# DX-HR.net
KiCad netlist of a schematic drawn in EAGLE
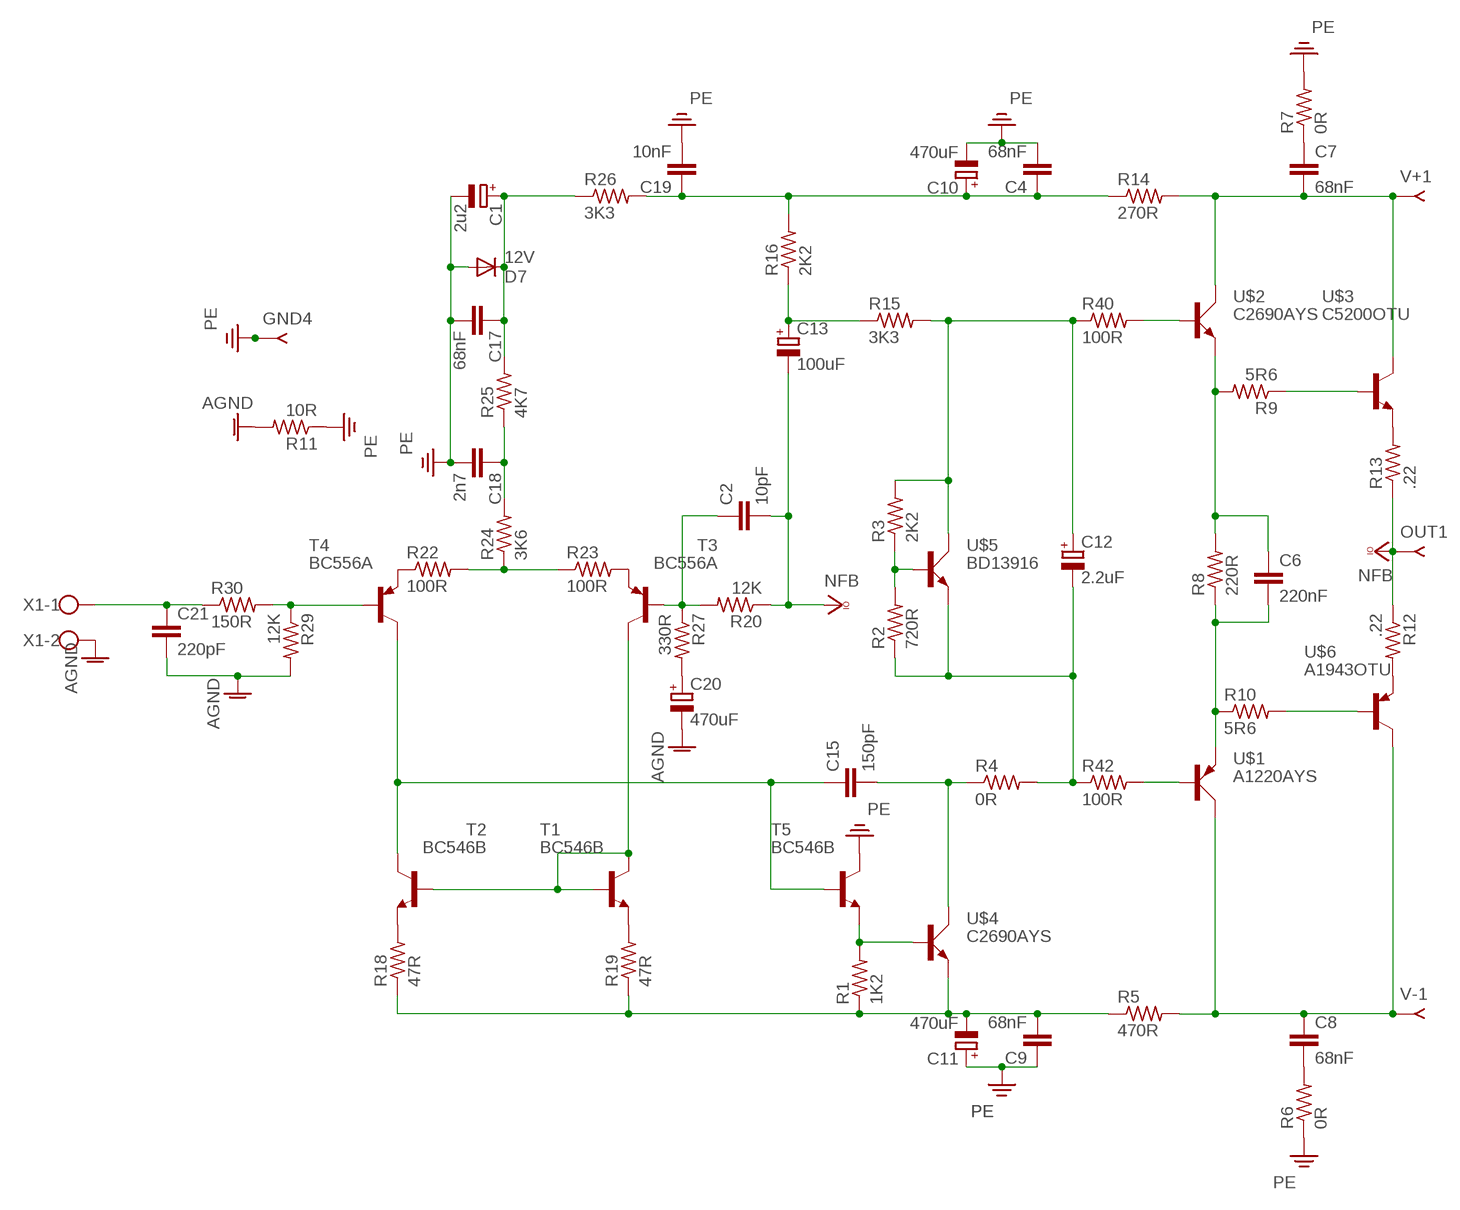
[diagram p0: schematic, sheet 1]

(export (version "E")
  (design (tool "Eeschema 10.0.6"))
  (components
    (comp (ref "C1")
      (value "2u2")
      (footprint "eagle-import:E3,5-8")
      (libsource (lib "eagle-import") (part "CPOL-EUE3.5-8"))
    )
    (comp (ref "C2")
      (value "10pF")
      (footprint "eagle-import:C102-043X133")
      (libsource (lib "eagle-import") (part "C-EU102-043X133"))
    )
    (comp (ref "C4")
      (value "68nF")
      (footprint "eagle-import:C050-055X075")
      (libsource (lib "eagle-import") (part "C-EU050-055X075"))
    )
    (comp (ref "C6")
      (value "220nF")
      (footprint "eagle-import:C102-043X133")
      (libsource (lib "eagle-import") (part "C-EU102-043X133"))
    )
    (comp (ref "C7")
      (value "68nF")
      (footprint "eagle-import:C102-043X133")
      (libsource (lib "eagle-import") (part "C-EU102-043X133"))
    )
    (comp (ref "C8")
      (value "68nF")
      (footprint "eagle-import:C102-043X133")
      (libsource (lib "eagle-import") (part "C-EU102-043X133"))
    )
    (comp (ref "C9")
      (value "68nF")
      (footprint "eagle-import:C050-055X075")
      (libsource (lib "eagle-import") (part "C-EU050-055X075"))
    )
    (comp (ref "C10")
      (value "470uF")
      (footprint "eagle-import:E5-13")
      (libsource (lib "eagle-import") (part "CPOL-EUE5-13"))
    )
    (comp (ref "C11")
      (value "470uF")
      (footprint "eagle-import:E5-13")
      (libsource (lib "eagle-import") (part "CPOL-EUE5-13"))
    )
    (comp (ref "C12")
      (value "2.2uF")
      (footprint "eagle-import:E3,5-8")
      (libsource (lib "eagle-import") (part "CPOL-EUE3.5-8"))
    )
    (comp (ref "C13")
      (value "100uF")
      (footprint "eagle-import:E5-10,5")
      (libsource (lib "eagle-import") (part "CPOL-EUE5-10.5"))
    )
    (comp (ref "C15")
      (value "150pF")
      (footprint "eagle-import:C102-043X133")
      (libsource (lib "eagle-import") (part "C-EU102-043X133"))
    )
    (comp (ref "C17")
      (value "68nF")
      (footprint "eagle-import:C050-035X075")
      (libsource (lib "eagle-import") (part "C-EU050-035X075"))
    )
    (comp (ref "C18")
      (value "2n7")
      (footprint "eagle-import:C050-055X075")
      (libsource (lib "eagle-import") (part "C-EU050-055X075"))
    )
    (comp (ref "C19")
      (value "10nF")
      (footprint "eagle-import:C050-055X075")
      (libsource (lib "eagle-import") (part "C-EU050-055X075"))
    )
    (comp (ref "C20")
      (value "470uF")
      (footprint "eagle-import:E5-10,5")
      (libsource (lib "eagle-import") (part "CPOL-EUE5-10.5"))
    )
    (comp (ref "C21")
      (value "220pF")
      (footprint "eagle-import:C050-055X075")
      (libsource (lib "eagle-import") (part "C-EU050-055X075"))
    )
    (comp (ref "D7")
      (value "12V")
      (footprint "eagle-import:DO41-10")
      (libsource (lib "eagle-import") (part "1N4004"))
    )
    (comp (ref "GND4")
      (value "GND")
      (footprint "eagle-import:FASTON")
      (libsource (lib "eagle-import") (part "QFIT"))
    )
    (comp (ref "OUT1")
      (value "QFIT")
      (footprint "eagle-import:FASTON")
      (libsource (lib "eagle-import") (part "QFIT"))
    )
    (comp (ref "R1")
      (value "1K2")
      (footprint "eagle-import:0309_12")
      (libsource (lib "eagle-import") (part "R-US_0309/12"))
    )
    (comp (ref "R2")
      (value "720R")
      (footprint "eagle-import:0309_12")
      (libsource (lib "eagle-import") (part "R-US_0309/12"))
    )
    (comp (ref "R3")
      (value "2K2")
      (footprint "eagle-import:0309_10")
      (libsource (lib "eagle-import") (part "R-US_0309/10"))
    )
    (comp (ref "R4")
      (value "0R")
      (footprint "eagle-import:0309_12")
      (libsource (lib "eagle-import") (part "R-US_0309/12"))
    )
    (comp (ref "R5")
      (value "470R")
      (footprint "eagle-import:0617_22")
      (libsource (lib "eagle-import") (part "R-US_0617/22"))
    )
    (comp (ref "R6")
      (value "0R")
      (footprint "eagle-import:0309_12")
      (libsource (lib "eagle-import") (part "R-US_0309/12"))
    )
    (comp (ref "R7")
      (value "0R")
      (footprint "eagle-import:0309_12")
      (libsource (lib "eagle-import") (part "R-US_0309/12"))
    )
    (comp (ref "R8")
      (value "220R")
      (footprint "eagle-import:0309_12")
      (libsource (lib "eagle-import") (part "R-US_0309/12"))
    )
    (comp (ref "R9")
      (value "5R6")
      (footprint "eagle-import:0309_12")
      (libsource (lib "eagle-import") (part "R-US_0309/12"))
    )
    (comp (ref "R10")
      (value "5R6")
      (footprint "eagle-import:0309_12")
      (libsource (lib "eagle-import") (part "R-US_0309/12"))
    )
    (comp (ref "R11")
      (value "10R")
      (footprint "eagle-import:0309_12")
      (libsource (lib "eagle-import") (part "R-US_0309/12"))
    )
    (comp (ref "R12")
      (value ".22")
      (footprint "eagle-import:0617_22")
      (libsource (lib "eagle-import") (part "R-US_0617/22"))
    )
    (comp (ref "R13")
      (value ".22")
      (footprint "eagle-import:0617_22")
      (libsource (lib "eagle-import") (part "R-US_0617/22"))
    )
    (comp (ref "R14")
      (value "270R")
      (footprint "eagle-import:0617_22")
      (libsource (lib "eagle-import") (part "R-US_0617/22"))
    )
    (comp (ref "R15")
      (value "3K3")
      (footprint "eagle-import:0309_12")
      (libsource (lib "eagle-import") (part "R-US_0309/12"))
    )
    (comp (ref "R16")
      (value "2K2")
      (footprint "eagle-import:0309_12")
      (libsource (lib "eagle-import") (part "R-US_0309/12"))
    )
    (comp (ref "R18")
      (value "47R")
      (footprint "eagle-import:0309_12")
      (libsource (lib "eagle-import") (part "R-US_0309/12"))
    )
    (comp (ref "R19")
      (value "47R")
      (footprint "eagle-import:0309_12")
      (libsource (lib "eagle-import") (part "R-US_0309/12"))
    )
    (comp (ref "R20")
      (value "12K")
      (footprint "eagle-import:0309_12")
      (libsource (lib "eagle-import") (part "R-US_0309/12"))
    )
    (comp (ref "R22")
      (value "100R")
      (footprint "eagle-import:0309_12")
      (libsource (lib "eagle-import") (part "R-US_0309/12"))
    )
    (comp (ref "R23")
      (value "100R")
      (footprint "eagle-import:0309_12")
      (libsource (lib "eagle-import") (part "R-US_0309/12"))
    )
    (comp (ref "R24")
      (value "3K6")
      (footprint "eagle-import:0309_12")
      (libsource (lib "eagle-import") (part "R-US_0309/12"))
    )
    (comp (ref "R25")
      (value "4K7")
      (footprint "eagle-import:0309_12")
      (libsource (lib "eagle-import") (part "R-US_0309/12"))
    )
    (comp (ref "R26")
      (value "3K3")
      (footprint "eagle-import:0309_12")
      (libsource (lib "eagle-import") (part "R-US_0309/12"))
    )
    (comp (ref "R27")
      (value "330R")
      (footprint "eagle-import:0309_12")
      (libsource (lib "eagle-import") (part "R-US_0309/12"))
    )
    (comp (ref "R29")
      (value "12K")
      (footprint "eagle-import:0309_12")
      (libsource (lib "eagle-import") (part "R-US_0309/12"))
    )
    (comp (ref "R30")
      (value "150R")
      (footprint "eagle-import:0309_12")
      (libsource (lib "eagle-import") (part "R-US_0309/12"))
    )
    (comp (ref "R40")
      (value "100R")
      (footprint "eagle-import:0309_10")
      (libsource (lib "eagle-import") (part "R-US_0309/10"))
    )
    (comp (ref "R42")
      (value "100R")
      (footprint "eagle-import:0309_10")
      (libsource (lib "eagle-import") (part "R-US_0309/10"))
    )
    (comp (ref "T1")
      (value "BC546B")
      (footprint "eagle-import:TO92-CBE")
      (libsource (lib "eagle-import") (part "-NPN-TO92-CBE"))
    )
    (comp (ref "T2")
      (value "BC546B")
      (footprint "eagle-import:TO92-CBE")
      (libsource (lib "eagle-import") (part "-NPN-TO92-CBE"))
    )
    (comp (ref "T3")
      (value "BC556A")
      (footprint "eagle-import:TO92-CBE")
      (libsource (lib "eagle-import") (part "-PNP-TO92-CBE"))
    )
    (comp (ref "T4")
      (value "BC556A")
      (footprint "eagle-import:TO92-CBE")
      (libsource (lib "eagle-import") (part "-PNP-TO92-CBE"))
    )
    (comp (ref "T5")
      (value "BC546B")
      (footprint "eagle-import:TO92-CBE")
      (libsource (lib "eagle-import") (part "-NPN-TO92-CBE"))
    )
    (comp (ref "U$1")
      (value "A1220AYS")
      (footprint "eagle-import:TO220AV")
      (libsource (lib "eagle-import") (part "TIP42C"))
    )
    (comp (ref "U$2")
      (value "C2690AYS")
      (footprint "eagle-import:TO220AV")
      (libsource (lib "eagle-import") (part "TIP41C"))
    )
    (comp (ref "U$3")
      (value "C5200OTU")
      (footprint "eagle-import:TO-264")
      (libsource (lib "eagle-import") (part "MJL4281"))
    )
    (comp (ref "U$4")
      (value "C2690AYS")
      (footprint "eagle-import:TO220AV")
      (libsource (lib "eagle-import") (part "TIP41C"))
    )
    (comp (ref "U$5")
      (value "BD13916")
      (footprint "eagle-import:TO220AV")
      (libsource (lib "eagle-import") (part "TIP41C"))
    )
    (comp (ref "U$6")
      (value "A1943OTU")
      (footprint "eagle-import:TO-264")
      (libsource (lib "eagle-import") (part "MJL4302"))
    )
    (comp (ref "V+1")
      (value "QFIT")
      (footprint "eagle-import:FASTON")
      (libsource (lib "eagle-import") (part "QFIT"))
    )
    (comp (ref "V-1")
      (value "QFIT")
      (footprint "eagle-import:FASTON")
      (libsource (lib "eagle-import") (part "QFIT"))
    )
    (comp (ref "X1")
      (value "W237-02P")
      (footprint "eagle-import:W237-132")
      (libsource (lib "eagle-import") (part "W237-02P"))
    )
  )
  (nets
    (net (code "1") (name "AGND") (class "Default")
      (node (ref "C20") (pin "-") (pinfunction "-_-") (pintype "passive"))
      (node (ref "C21") (pin "2") (pinfunction "2_2") (pintype "passive"))
      (node (ref "R11") (pin "2") (pinfunction "2_2") (pintype "passive"))
      (node (ref "R29") (pin "2") (pinfunction "2_2") (pintype "passive"))
      (node (ref "X1") (pin "2") (pinfunction "KL_2") (pintype "passive"))
    )
    (net (code "2") (name "NFB") (class "Default")
      (node (ref "C13") (pin "-") (pinfunction "-_-") (pintype "passive"))
      (node (ref "C2") (pin "2") (pinfunction "2_2") (pintype "passive"))
      (node (ref "OUT1") (pin "1") (pinfunction "1_1") (pintype "passive"))
      (node (ref "OUT1") (pin "2") (pinfunction "2_2") (pintype "passive"))
      (node (ref "R12") (pin "1") (pinfunction "1_1") (pintype "passive"))
      (node (ref "R13") (pin "1") (pinfunction "1_1") (pintype "passive"))
      (node (ref "R20") (pin "1") (pinfunction "1_1") (pintype "passive"))
    )
    (net (code "3") (name "Net-(C1-Pad+)") (class "Default")
      (node (ref "C1") (pin "+") (pinfunction "+_+") (pintype "passive"))
      (node (ref "C17") (pin "1") (pinfunction "1_1") (pintype "passive"))
      (node (ref "D7") (pin "C") (pinfunction "C_C") (pintype "passive"))
      (node (ref "R25") (pin "2") (pinfunction "2_2") (pintype "passive"))
      (node (ref "R26") (pin "1") (pinfunction "1_1") (pintype "passive"))
    )
    (net (code "4") (name "Net-(C2-Pad1)") (class "Default")
      (node (ref "C2") (pin "1") (pinfunction "1_1") (pintype "passive"))
      (node (ref "R20") (pin "2") (pinfunction "2_2") (pintype "passive"))
      (node (ref "R27") (pin "1") (pinfunction "1_1") (pintype "passive"))
      (node (ref "T3") (pin "B") (pinfunction "B_B") (pintype "passive"))
    )
    (net (code "5") (name "Net-(C6-Pad1)") (class "Default")
      (node (ref "C6") (pin "1") (pinfunction "1_1") (pintype "passive"))
      (node (ref "R8") (pin "2") (pinfunction "2_2") (pintype "passive"))
      (node (ref "R9") (pin "2") (pinfunction "2_2") (pintype "passive"))
      (node (ref "U$2") (pin "E") (pinfunction "E_E") (pintype "passive"))
    )
    (net (code "6") (name "Net-(C6-Pad2)") (class "Default")
      (node (ref "C6") (pin "2") (pinfunction "2_2") (pintype "passive"))
      (node (ref "R10") (pin "1") (pinfunction "1_1") (pintype "passive"))
      (node (ref "R8") (pin "1") (pinfunction "1_1") (pintype "passive"))
      (node (ref "U$1") (pin "E") (pinfunction "E_E") (pintype "passive"))
    )
    (net (code "7") (name "Net-(C7-Pad1)") (class "Default")
      (node (ref "C7") (pin "1") (pinfunction "1_1") (pintype "passive"))
      (node (ref "R7") (pin "1") (pinfunction "1_1") (pintype "passive"))
    )
    (net (code "8") (name "Net-(C7-Pad2)") (class "Default")
      (node (ref "C7") (pin "2") (pinfunction "2_2") (pintype "passive"))
      (node (ref "R14") (pin "2") (pinfunction "2_2") (pintype "passive"))
      (node (ref "U$2") (pin "C") (pinfunction "C_C") (pintype "passive"))
      (node (ref "U$3") (pin "C") (pinfunction "C_C") (pintype "passive"))
      (node (ref "V+1") (pin "1") (pinfunction "1_1") (pintype "passive"))
      (node (ref "V+1") (pin "2") (pinfunction "2_2") (pintype "passive"))
    )
    (net (code "9") (name "Net-(C8-Pad1)") (class "Default")
      (node (ref "C8") (pin "1") (pinfunction "1_1") (pintype "passive"))
      (node (ref "R5") (pin "2") (pinfunction "2_2") (pintype "passive"))
      (node (ref "U$1") (pin "C") (pinfunction "C_C") (pintype "passive"))
      (node (ref "U$6") (pin "C") (pinfunction "C_C") (pintype "passive"))
      (node (ref "V-1") (pin "1") (pinfunction "1_1") (pintype "passive"))
      (node (ref "V-1") (pin "2") (pinfunction "2_2") (pintype "passive"))
    )
    (net (code "10") (name "Net-(C8-Pad2)") (class "Default")
      (node (ref "C8") (pin "2") (pinfunction "2_2") (pintype "passive"))
      (node (ref "R6") (pin "2") (pinfunction "2_2") (pintype "passive"))
    )
    (net (code "11") (name "Net-(C10-Pad+)") (class "Default")
      (node (ref "C10") (pin "+") (pinfunction "+_+") (pintype "passive"))
      (node (ref "C19") (pin "1") (pinfunction "1_1") (pintype "passive"))
      (node (ref "C4") (pin "1") (pinfunction "1_1") (pintype "passive"))
      (node (ref "R14") (pin "1") (pinfunction "1_1") (pintype "passive"))
      (node (ref "R16") (pin "2") (pinfunction "2_2") (pintype "passive"))
      (node (ref "R26") (pin "2") (pinfunction "2_2") (pintype "passive"))
    )
    (net (code "12") (name "Net-(C11-Pad-)") (class "Default")
      (node (ref "C11") (pin "-") (pinfunction "-_-") (pintype "passive"))
      (node (ref "C9") (pin "2") (pinfunction "2_2") (pintype "passive"))
      (node (ref "R1") (pin "1") (pinfunction "1_1") (pintype "passive"))
      (node (ref "R18") (pin "1") (pinfunction "1_1") (pintype "passive"))
      (node (ref "R19") (pin "1") (pinfunction "1_1") (pintype "passive"))
      (node (ref "R5") (pin "1") (pinfunction "1_1") (pintype "passive"))
      (node (ref "U$4") (pin "E") (pinfunction "E_E") (pintype "passive"))
    )
    (net (code "13") (name "Net-(C12-Pad+)") (class "Default")
      (node (ref "C12") (pin "+") (pinfunction "+_+") (pintype "passive"))
      (node (ref "R15") (pin "2") (pinfunction "2_2") (pintype "passive"))
      (node (ref "R3") (pin "2") (pinfunction "2_2") (pintype "passive"))
      (node (ref "R40") (pin "1") (pinfunction "1_1") (pintype "passive"))
      (node (ref "U$5") (pin "C") (pinfunction "C_C") (pintype "passive"))
    )
    (net (code "14") (name "Net-(C12-Pad-)") (class "Default")
      (node (ref "C12") (pin "-") (pinfunction "-_-") (pintype "passive"))
      (node (ref "R2") (pin "1") (pinfunction "1_1") (pintype "passive"))
      (node (ref "R4") (pin "2") (pinfunction "2_2") (pintype "passive"))
      (node (ref "R42") (pin "1") (pinfunction "1_1") (pintype "passive"))
      (node (ref "U$5") (pin "E") (pinfunction "E_E") (pintype "passive"))
    )
    (net (code "15") (name "Net-(C13-Pad+)") (class "Default")
      (node (ref "C13") (pin "+") (pinfunction "+_+") (pintype "passive"))
      (node (ref "R15") (pin "1") (pinfunction "1_1") (pintype "passive"))
      (node (ref "R16") (pin "1") (pinfunction "1_1") (pintype "passive"))
    )
    (net (code "16") (name "Net-(C15-Pad1)") (class "Default")
      (node (ref "C15") (pin "1") (pinfunction "1_1") (pintype "passive"))
      (node (ref "T2") (pin "C") (pinfunction "C_C") (pintype "passive"))
      (node (ref "T4") (pin "C") (pinfunction "C_C") (pintype "passive"))
      (node (ref "T5") (pin "B") (pinfunction "B_B") (pintype "passive"))
    )
    (net (code "17") (name "Net-(C15-Pad2)") (class "Default")
      (node (ref "C15") (pin "2") (pinfunction "2_2") (pintype "passive"))
      (node (ref "R4") (pin "1") (pinfunction "1_1") (pintype "passive"))
      (node (ref "U$4") (pin "C") (pinfunction "C_C") (pintype "passive"))
    )
    (net (code "18") (name "Net-(C18-Pad1)") (class "Default")
      (node (ref "C18") (pin "1") (pinfunction "1_1") (pintype "passive"))
      (node (ref "R24") (pin "2") (pinfunction "2_2") (pintype "passive"))
      (node (ref "R25") (pin "1") (pinfunction "1_1") (pintype "passive"))
    )
    (net (code "19") (name "Net-(C20-Pad+)") (class "Default")
      (node (ref "C20") (pin "+") (pinfunction "+_+") (pintype "passive"))
      (node (ref "R27") (pin "2") (pinfunction "2_2") (pintype "passive"))
    )
    (net (code "20") (name "Net-(R1-Pad2)") (class "Default")
      (node (ref "R1") (pin "2") (pinfunction "2_2") (pintype "passive"))
      (node (ref "T5") (pin "E") (pinfunction "E_E") (pintype "passive"))
      (node (ref "U$4") (pin "B") (pinfunction "B_B") (pintype "passive"))
    )
    (net (code "21") (name "Net-(R2-Pad2)") (class "Default")
      (node (ref "R2") (pin "2") (pinfunction "2_2") (pintype "passive"))
      (node (ref "R3") (pin "1") (pinfunction "1_1") (pintype "passive"))
      (node (ref "U$5") (pin "B") (pinfunction "B_B") (pintype "passive"))
    )
    (net (code "22") (name "Net-(R9-Pad1)") (class "Default")
      (node (ref "R9") (pin "1") (pinfunction "1_1") (pintype "passive"))
      (node (ref "U$3") (pin "B") (pinfunction "B_B") (pintype "passive"))
    )
    (net (code "23") (name "Net-(R10-Pad2)") (class "Default")
      (node (ref "R10") (pin "2") (pinfunction "2_2") (pintype "passive"))
      (node (ref "U$6") (pin "B") (pinfunction "B_B") (pintype "passive"))
    )
    (net (code "24") (name "Net-(R12-Pad2)") (class "Default")
      (node (ref "R12") (pin "2") (pinfunction "2_2") (pintype "passive"))
      (node (ref "U$6") (pin "E") (pinfunction "E_E") (pintype "passive"))
    )
    (net (code "25") (name "Net-(R13-Pad2)") (class "Default")
      (node (ref "R13") (pin "2") (pinfunction "2_2") (pintype "passive"))
      (node (ref "U$3") (pin "E") (pinfunction "E_E") (pintype "passive"))
    )
    (net (code "26") (name "Net-(R18-Pad2)") (class "Default")
      (node (ref "R18") (pin "2") (pinfunction "2_2") (pintype "passive"))
      (node (ref "T2") (pin "E") (pinfunction "E_E") (pintype "passive"))
    )
    (net (code "27") (name "Net-(R19-Pad2)") (class "Default")
      (node (ref "R19") (pin "2") (pinfunction "2_2") (pintype "passive"))
      (node (ref "T1") (pin "E") (pinfunction "E_E") (pintype "passive"))
    )
    (net (code "28") (name "Net-(R22-Pad1)") (class "Default")
      (node (ref "R22") (pin "1") (pinfunction "1_1") (pintype "passive"))
      (node (ref "T4") (pin "E") (pinfunction "E_E") (pintype "passive"))
    )
    (net (code "29") (name "Net-(R22-Pad2)") (class "Default")
      (node (ref "R22") (pin "2") (pinfunction "2_2") (pintype "passive"))
      (node (ref "R23") (pin "1") (pinfunction "1_1") (pintype "passive"))
      (node (ref "R24") (pin "1") (pinfunction "1_1") (pintype "passive"))
    )
    (net (code "30") (name "Net-(R23-Pad2)") (class "Default")
      (node (ref "R23") (pin "2") (pinfunction "2_2") (pintype "passive"))
      (node (ref "T3") (pin "E") (pinfunction "E_E") (pintype "passive"))
    )
    (net (code "31") (name "Net-(R29-Pad1)") (class "Default")
      (node (ref "R29") (pin "1") (pinfunction "1_1") (pintype "passive"))
      (node (ref "R30") (pin "2") (pinfunction "2_2") (pintype "passive"))
      (node (ref "T4") (pin "B") (pinfunction "B_B") (pintype "passive"))
    )
    (net (code "32") (name "Net-(R40-Pad2)") (class "Default")
      (node (ref "R40") (pin "2") (pinfunction "2_2") (pintype "passive"))
      (node (ref "U$2") (pin "B") (pinfunction "B_B") (pintype "passive"))
    )
    (net (code "33") (name "Net-(R42-Pad2)") (class "Default")
      (node (ref "R42") (pin "2") (pinfunction "2_2") (pintype "passive"))
      (node (ref "U$1") (pin "B") (pinfunction "B_B") (pintype "passive"))
    )
    (net (code "34") (name "Net-(T1-PadB)") (class "Default")
      (node (ref "T1") (pin "B") (pinfunction "B_B") (pintype "passive"))
      (node (ref "T1") (pin "C") (pinfunction "C_C") (pintype "passive"))
      (node (ref "T2") (pin "B") (pinfunction "B_B") (pintype "passive"))
      (node (ref "T3") (pin "C") (pinfunction "C_C") (pintype "passive"))
    )
    (net (code "35") (name "Net-(X1A-KL)") (class "Default")
      (node (ref "C21") (pin "1") (pinfunction "1_1") (pintype "passive"))
      (node (ref "R30") (pin "1") (pinfunction "1_1") (pintype "passive"))
      (node (ref "X1") (pin "1") (pinfunction "KL_1") (pintype "passive"))
    )
    (net (code "36") (name "PE") (class "Default")
      (node (ref "C1") (pin "-") (pinfunction "-_-") (pintype "passive"))
      (node (ref "C10") (pin "-") (pinfunction "-_-") (pintype "passive"))
      (node (ref "C11") (pin "+") (pinfunction "+_+") (pintype "passive"))
      (node (ref "C17") (pin "2") (pinfunction "2_2") (pintype "passive"))
      (node (ref "C18") (pin "2") (pinfunction "2_2") (pintype "passive"))
      (node (ref "C19") (pin "2") (pinfunction "2_2") (pintype "passive"))
      (node (ref "C4") (pin "2") (pinfunction "2_2") (pintype "passive"))
      (node (ref "C9") (pin "1") (pinfunction "1_1") (pintype "passive"))
      (node (ref "D7") (pin "A") (pinfunction "A_A") (pintype "passive"))
      (node (ref "GND4") (pin "1") (pinfunction "1_1") (pintype "passive"))
      (node (ref "GND4") (pin "2") (pinfunction "2_2") (pintype "passive"))
      (node (ref "R11") (pin "1") (pinfunction "1_1") (pintype "passive"))
      (node (ref "R6") (pin "1") (pinfunction "1_1") (pintype "passive"))
      (node (ref "R7") (pin "2") (pinfunction "2_2") (pintype "passive"))
      (node (ref "T5") (pin "C") (pinfunction "C_C") (pintype "passive"))
    )
  )
)
